# CubeShield.net
KiCad netlist of a schematic drawn in EAGLE
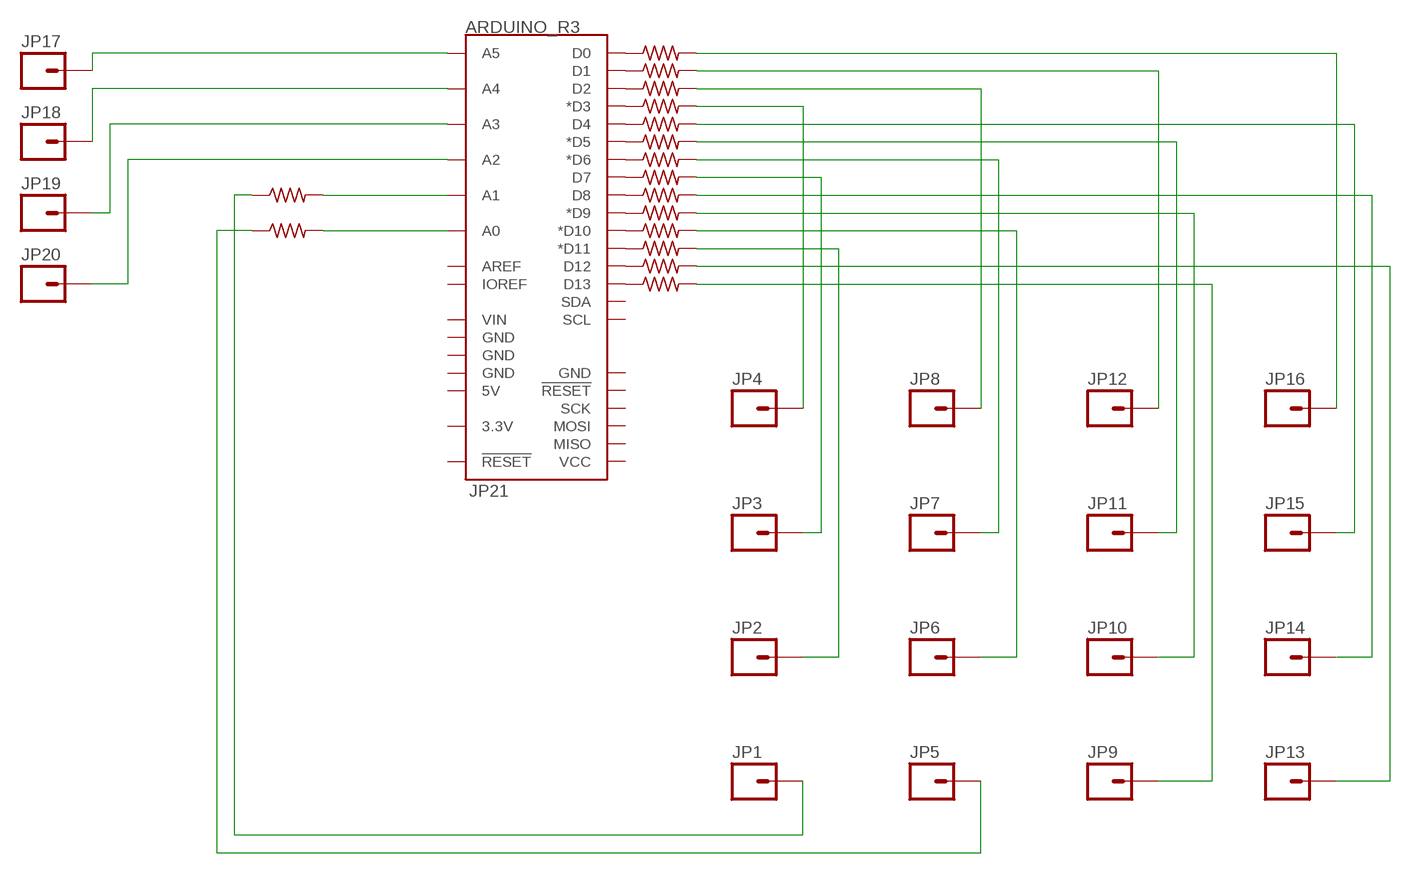
[diagram p0: schematic, sheet 1]

(export (version "E")
  (design (tool "Eeschema 10.0.6"))
  (components
    (comp (ref "JP1")
      (value "M01PTH_LONGPAD")
      (footprint "eagle-import:1X01_LONGPAD")
      (libsource (lib "eagle-import") (part "M01PTH_LONGPAD"))
    )
    (comp (ref "JP2")
      (value "M01PTH_LONGPAD")
      (footprint "eagle-import:1X01_LONGPAD")
      (libsource (lib "eagle-import") (part "M01PTH_LONGPAD"))
    )
    (comp (ref "JP3")
      (value "M01PTH_LONGPAD")
      (footprint "eagle-import:1X01_LONGPAD")
      (libsource (lib "eagle-import") (part "M01PTH_LONGPAD"))
    )
    (comp (ref "JP4")
      (value "M01PTH_LONGPAD")
      (footprint "eagle-import:1X01_LONGPAD")
      (libsource (lib "eagle-import") (part "M01PTH_LONGPAD"))
    )
    (comp (ref "JP5")
      (value "M01PTH_LONGPAD")
      (footprint "eagle-import:1X01_LONGPAD")
      (libsource (lib "eagle-import") (part "M01PTH_LONGPAD"))
    )
    (comp (ref "JP6")
      (value "M01PTH_LONGPAD")
      (footprint "eagle-import:1X01_LONGPAD")
      (libsource (lib "eagle-import") (part "M01PTH_LONGPAD"))
    )
    (comp (ref "JP7")
      (value "M01PTH_LONGPAD")
      (footprint "eagle-import:1X01_LONGPAD")
      (libsource (lib "eagle-import") (part "M01PTH_LONGPAD"))
    )
    (comp (ref "JP8")
      (value "M01PTH_LONGPAD")
      (footprint "eagle-import:1X01_LONGPAD")
      (libsource (lib "eagle-import") (part "M01PTH_LONGPAD"))
    )
    (comp (ref "JP9")
      (value "M01PTH_LONGPAD")
      (footprint "eagle-import:1X01_LONGPAD")
      (libsource (lib "eagle-import") (part "M01PTH_LONGPAD"))
    )
    (comp (ref "JP10")
      (value "M01PTH_LONGPAD")
      (footprint "eagle-import:1X01_LONGPAD")
      (libsource (lib "eagle-import") (part "M01PTH_LONGPAD"))
    )
    (comp (ref "JP11")
      (value "M01PTH_LONGPAD")
      (footprint "eagle-import:1X01_LONGPAD")
      (libsource (lib "eagle-import") (part "M01PTH_LONGPAD"))
    )
    (comp (ref "JP12")
      (value "M01PTH_LONGPAD")
      (footprint "eagle-import:1X01_LONGPAD")
      (libsource (lib "eagle-import") (part "M01PTH_LONGPAD"))
    )
    (comp (ref "JP13")
      (value "M01PTH_LONGPAD")
      (footprint "eagle-import:1X01_LONGPAD")
      (libsource (lib "eagle-import") (part "M01PTH_LONGPAD"))
    )
    (comp (ref "JP14")
      (value "M01PTH_LONGPAD")
      (footprint "eagle-import:1X01_LONGPAD")
      (libsource (lib "eagle-import") (part "M01PTH_LONGPAD"))
    )
    (comp (ref "JP15")
      (value "M01PTH_LONGPAD")
      (footprint "eagle-import:1X01_LONGPAD")
      (libsource (lib "eagle-import") (part "M01PTH_LONGPAD"))
    )
    (comp (ref "JP16")
      (value "M01PTH_LONGPAD")
      (footprint "eagle-import:1X01_LONGPAD")
      (libsource (lib "eagle-import") (part "M01PTH_LONGPAD"))
    )
    (comp (ref "JP17")
      (value "M01PTH_LONGPAD")
      (footprint "eagle-import:1X01_LONGPAD")
      (libsource (lib "eagle-import") (part "M01PTH_LONGPAD"))
    )
    (comp (ref "JP18")
      (value "M01PTH_LONGPAD")
      (footprint "eagle-import:1X01_LONGPAD")
      (libsource (lib "eagle-import") (part "M01PTH_LONGPAD"))
    )
    (comp (ref "JP19")
      (value "M01PTH_LONGPAD")
      (footprint "eagle-import:1X01_LONGPAD")
      (libsource (lib "eagle-import") (part "M01PTH_LONGPAD"))
    )
    (comp (ref "JP20")
      (value "M01PTH_LONGPAD")
      (footprint "eagle-import:1X01_LONGPAD")
      (libsource (lib "eagle-import") (part "M01PTH_LONGPAD"))
    )
    (comp (ref "JP21")
      (value "ARDUINO_R3")
      (footprint "eagle-import:ARDUINO_R3")
      (libsource (lib "eagle-import") (part "ARDUINO_R3"))
    )
    (comp (ref "R1")
      (value "R-US_0207/7")
      (footprint "eagle-import:0207_7")
      (libsource (lib "eagle-import") (part "R-US_0207/7"))
    )
    (comp (ref "R2")
      (value "R-US_0207/7")
      (footprint "eagle-import:0207_7")
      (libsource (lib "eagle-import") (part "R-US_0207/7"))
    )
    (comp (ref "R3")
      (value "R-US_0207/7")
      (footprint "eagle-import:0207_7")
      (libsource (lib "eagle-import") (part "R-US_0207/7"))
    )
    (comp (ref "R4")
      (value "R-US_0207/7")
      (footprint "eagle-import:0207_7")
      (libsource (lib "eagle-import") (part "R-US_0207/7"))
    )
    (comp (ref "R5")
      (value "R-US_0207/7")
      (footprint "eagle-import:0207_7")
      (libsource (lib "eagle-import") (part "R-US_0207/7"))
    )
    (comp (ref "R6")
      (value "R-US_0207/7")
      (footprint "eagle-import:0207_7")
      (libsource (lib "eagle-import") (part "R-US_0207/7"))
    )
    (comp (ref "R7")
      (value "R-US_0207/7")
      (footprint "eagle-import:0207_7")
      (libsource (lib "eagle-import") (part "R-US_0207/7"))
    )
    (comp (ref "R8")
      (value "R-US_0207/7")
      (footprint "eagle-import:0207_7")
      (libsource (lib "eagle-import") (part "R-US_0207/7"))
    )
    (comp (ref "R9")
      (value "R-US_0207/7")
      (footprint "eagle-import:0207_7")
      (libsource (lib "eagle-import") (part "R-US_0207/7"))
    )
    (comp (ref "R10")
      (value "R-US_0207/7")
      (footprint "eagle-import:0207_7")
      (libsource (lib "eagle-import") (part "R-US_0207/7"))
    )
    (comp (ref "R11")
      (value "R-US_0207/7")
      (footprint "eagle-import:0207_7")
      (libsource (lib "eagle-import") (part "R-US_0207/7"))
    )
    (comp (ref "R12")
      (value "R-US_0207/7")
      (footprint "eagle-import:0207_7")
      (libsource (lib "eagle-import") (part "R-US_0207/7"))
    )
    (comp (ref "R13")
      (value "R-US_0207/7")
      (footprint "eagle-import:0207_7")
      (libsource (lib "eagle-import") (part "R-US_0207/7"))
    )
    (comp (ref "R14")
      (value "R-US_0207/7")
      (footprint "eagle-import:0207_7")
      (libsource (lib "eagle-import") (part "R-US_0207/7"))
    )
    (comp (ref "R15")
      (value "R-US_0207/7")
      (footprint "eagle-import:0207_7")
      (libsource (lib "eagle-import") (part "R-US_0207/7"))
    )
    (comp (ref "R16")
      (value "R-US_0207/7")
      (footprint "eagle-import:0207_7")
      (libsource (lib "eagle-import") (part "R-US_0207/7"))
    )
  )
  (nets
    (net (code "1") (name "Net-(JP1-Pad1)") (class "Default")
      (node (ref "JP1") (pin "1") (pinfunction "1_1") (pintype "passive"))
      (node (ref "R16") (pin "1") (pinfunction "1_1") (pintype "passive"))
    )
    (net (code "2") (name "Net-(JP2-Pad1)") (class "Default")
      (node (ref "JP2") (pin "1") (pinfunction "1_1") (pintype "passive"))
      (node (ref "R12") (pin "2") (pinfunction "2_2") (pintype "passive"))
    )
    (net (code "3") (name "Net-(JP3-Pad1)") (class "Default")
      (node (ref "JP3") (pin "1") (pinfunction "1_1") (pintype "passive"))
      (node (ref "R8") (pin "2") (pinfunction "2_2") (pintype "passive"))
    )
    (net (code "4") (name "Net-(JP4-Pad1)") (class "Default")
      (node (ref "JP4") (pin "1") (pinfunction "1_1") (pintype "passive"))
      (node (ref "R4") (pin "2") (pinfunction "2_2") (pintype "passive"))
    )
    (net (code "5") (name "Net-(JP5-Pad1)") (class "Default")
      (node (ref "JP5") (pin "1") (pinfunction "1_1") (pintype "passive"))
      (node (ref "R15") (pin "1") (pinfunction "1_1") (pintype "passive"))
    )
    (net (code "6") (name "Net-(JP6-Pad1)") (class "Default")
      (node (ref "JP6") (pin "1") (pinfunction "1_1") (pintype "passive"))
      (node (ref "R11") (pin "2") (pinfunction "2_2") (pintype "passive"))
    )
    (net (code "7") (name "Net-(JP7-Pad1)") (class "Default")
      (node (ref "JP7") (pin "1") (pinfunction "1_1") (pintype "passive"))
      (node (ref "R7") (pin "2") (pinfunction "2_2") (pintype "passive"))
    )
    (net (code "8") (name "Net-(JP8-Pad1)") (class "Default")
      (node (ref "JP8") (pin "1") (pinfunction "1_1") (pintype "passive"))
      (node (ref "R3") (pin "2") (pinfunction "2_2") (pintype "passive"))
    )
    (net (code "9") (name "Net-(JP9-Pad1)") (class "Default")
      (node (ref "JP9") (pin "1") (pinfunction "1_1") (pintype "passive"))
      (node (ref "R14") (pin "2") (pinfunction "2_2") (pintype "passive"))
    )
    (net (code "10") (name "Net-(JP10-Pad1)") (class "Default")
      (node (ref "JP10") (pin "1") (pinfunction "1_1") (pintype "passive"))
      (node (ref "R10") (pin "2") (pinfunction "2_2") (pintype "passive"))
    )
    (net (code "11") (name "Net-(JP11-Pad1)") (class "Default")
      (node (ref "JP11") (pin "1") (pinfunction "1_1") (pintype "passive"))
      (node (ref "R6") (pin "2") (pinfunction "2_2") (pintype "passive"))
    )
    (net (code "12") (name "Net-(JP12-Pad1)") (class "Default")
      (node (ref "JP12") (pin "1") (pinfunction "1_1") (pintype "passive"))
      (node (ref "R2") (pin "2") (pinfunction "2_2") (pintype "passive"))
    )
    (net (code "13") (name "Net-(JP13-Pad1)") (class "Default")
      (node (ref "JP13") (pin "1") (pinfunction "1_1") (pintype "passive"))
      (node (ref "R13") (pin "2") (pinfunction "2_2") (pintype "passive"))
    )
    (net (code "14") (name "Net-(JP14-Pad1)") (class "Default")
      (node (ref "JP14") (pin "1") (pinfunction "1_1") (pintype "passive"))
      (node (ref "R9") (pin "2") (pinfunction "2_2") (pintype "passive"))
    )
    (net (code "15") (name "Net-(JP15-Pad1)") (class "Default")
      (node (ref "JP15") (pin "1") (pinfunction "1_1") (pintype "passive"))
      (node (ref "R5") (pin "2") (pinfunction "2_2") (pintype "passive"))
    )
    (net (code "16") (name "Net-(JP16-Pad1)") (class "Default")
      (node (ref "JP16") (pin "1") (pinfunction "1_1") (pintype "passive"))
      (node (ref "R1") (pin "2") (pinfunction "2_2") (pintype "passive"))
    )
    (net (code "17") (name "Net-(JP17-Pad1)") (class "Default")
      (node (ref "JP17") (pin "1") (pinfunction "1_1") (pintype "passive"))
      (node (ref "JP21") (pin "A5") (pinfunction "A5_A5") (pintype "bidirectional"))
    )
    (net (code "18") (name "Net-(JP18-Pad1)") (class "Default")
      (node (ref "JP18") (pin "1") (pinfunction "1_1") (pintype "passive"))
      (node (ref "JP21") (pin "A4") (pinfunction "A4_A4") (pintype "bidirectional"))
    )
    (net (code "19") (name "Net-(JP19-Pad1)") (class "Default")
      (node (ref "JP19") (pin "1") (pinfunction "1_1") (pintype "passive"))
      (node (ref "JP21") (pin "A3") (pinfunction "A3_A3") (pintype "bidirectional"))
    )
    (net (code "20") (name "Net-(JP20-Pad1)") (class "Default")
      (node (ref "JP20") (pin "1") (pinfunction "1_1") (pintype "passive"))
      (node (ref "JP21") (pin "A2") (pinfunction "A2_A2") (pintype "bidirectional"))
    )
    (net (code "21") (name "Net-(JP21-*D3)") (class "Default")
      (node (ref "JP21") (pin "D3") (pinfunction "*D3_D3") (pintype "bidirectional"))
      (node (ref "R4") (pin "1") (pinfunction "1_1") (pintype "passive"))
    )
    (net (code "22") (name "Net-(JP21-*D5)") (class "Default")
      (node (ref "JP21") (pin "D5") (pinfunction "*D5_D5") (pintype "bidirectional"))
      (node (ref "R6") (pin "1") (pinfunction "1_1") (pintype "passive"))
    )
    (net (code "23") (name "Net-(JP21-*D6)") (class "Default")
      (node (ref "JP21") (pin "D6") (pinfunction "*D6_D6") (pintype "bidirectional"))
      (node (ref "R7") (pin "1") (pinfunction "1_1") (pintype "passive"))
    )
    (net (code "24") (name "Net-(JP21-*D9)") (class "Default")
      (node (ref "JP21") (pin "D9") (pinfunction "*D9_D9") (pintype "bidirectional"))
      (node (ref "R10") (pin "1") (pinfunction "1_1") (pintype "passive"))
    )
    (net (code "25") (name "Net-(JP21-*D10)") (class "Default")
      (node (ref "JP21") (pin "D10") (pinfunction "*D10_D10") (pintype "bidirectional"))
      (node (ref "R11") (pin "1") (pinfunction "1_1") (pintype "passive"))
    )
    (net (code "26") (name "Net-(JP21-*D11)") (class "Default")
      (node (ref "JP21") (pin "D11") (pinfunction "*D11_D11") (pintype "bidirectional"))
      (node (ref "R12") (pin "1") (pinfunction "1_1") (pintype "passive"))
    )
    (net (code "27") (name "Net-(JP21-PadA0)") (class "Default")
      (node (ref "JP21") (pin "A0") (pinfunction "A0_A0") (pintype "bidirectional"))
      (node (ref "R15") (pin "2") (pinfunction "2_2") (pintype "passive"))
    )
    (net (code "28") (name "Net-(JP21-PadA1)") (class "Default")
      (node (ref "JP21") (pin "A1") (pinfunction "A1_A1") (pintype "bidirectional"))
      (node (ref "R16") (pin "2") (pinfunction "2_2") (pintype "passive"))
    )
    (net (code "29") (name "Net-(JP21-PadD0)") (class "Default")
      (node (ref "JP21") (pin "D0") (pinfunction "D0_D0") (pintype "bidirectional"))
      (node (ref "R1") (pin "1") (pinfunction "1_1") (pintype "passive"))
    )
    (net (code "30") (name "Net-(JP21-PadD1)") (class "Default")
      (node (ref "JP21") (pin "D1") (pinfunction "D1_D1") (pintype "bidirectional"))
      (node (ref "R2") (pin "1") (pinfunction "1_1") (pintype "passive"))
    )
    (net (code "31") (name "Net-(JP21-PadD2)") (class "Default")
      (node (ref "JP21") (pin "D2") (pinfunction "D2_D2") (pintype "bidirectional"))
      (node (ref "R3") (pin "1") (pinfunction "1_1") (pintype "passive"))
    )
    (net (code "32") (name "Net-(JP21-PadD4)") (class "Default")
      (node (ref "JP21") (pin "D4") (pinfunction "D4_D4") (pintype "bidirectional"))
      (node (ref "R5") (pin "1") (pinfunction "1_1") (pintype "passive"))
    )
    (net (code "33") (name "Net-(JP21-PadD7)") (class "Default")
      (node (ref "JP21") (pin "D7") (pinfunction "D7_D7") (pintype "bidirectional"))
      (node (ref "R8") (pin "1") (pinfunction "1_1") (pintype "passive"))
    )
    (net (code "34") (name "Net-(JP21-PadD8)") (class "Default")
      (node (ref "JP21") (pin "D8") (pinfunction "D8_D8") (pintype "bidirectional"))
      (node (ref "R9") (pin "1") (pinfunction "1_1") (pintype "passive"))
    )
    (net (code "35") (name "Net-(JP21-PadD12)") (class "Default")
      (node (ref "JP21") (pin "D12") (pinfunction "D12_D12") (pintype "bidirectional"))
      (node (ref "R13") (pin "1") (pinfunction "1_1") (pintype "passive"))
    )
    (net (code "36") (name "Net-(JP21-PadD13)") (class "Default")
      (node (ref "JP21") (pin "D13") (pinfunction "D13_D13") (pintype "bidirectional"))
      (node (ref "R14") (pin "1") (pinfunction "1_1") (pintype "passive"))
    )
    (net (code "37") (name "unconnected-(JP21-GND-PadGND@1)") (class "Default")
      (node (ref "JP21") (pin "GND@1") (pinfunction "GND_GND@1") (pintype "bidirectional"))
    )
    (net (code "38") (name "unconnected-(JP21-GND-PadGND@2)") (class "Default")
      (node (ref "JP21") (pin "GND@2") (pinfunction "GND_GND@2") (pintype "bidirectional"))
    )
    (net (code "39") (name "unconnected-(JP21-GND-PadGND@3)") (class "Default")
      (node (ref "JP21") (pin "GND@3") (pinfunction "GND_GND@3") (pintype "bidirectional"))
    )
    (net (code "40") (name "unconnected-(JP21-GND-PadGND@4)") (class "Default")
      (node (ref "JP21") (pin "GND@4") (pinfunction "GND_GND@4") (pintype "bidirectional"))
    )
    (net (code "41") (name "unconnected-(JP21-Pad3.3V)") (class "Default")
      (node (ref "JP21") (pin "3.3V") (pinfunction "3.3V_3.3V") (pintype "bidirectional"))
    )
    (net (code "42") (name "unconnected-(JP21-Pad5V)") (class "Default")
      (node (ref "JP21") (pin "5V") (pinfunction "5V_5V") (pintype "bidirectional"))
    )
    (net (code "43") (name "unconnected-(JP21-PadAREF)") (class "Default")
      (node (ref "JP21") (pin "AREF") (pinfunction "AREF_AREF") (pintype "bidirectional"))
    )
    (net (code "44") (name "unconnected-(JP21-PadIOREF)") (class "Default")
      (node (ref "JP21") (pin "IOREF") (pinfunction "IOREF_IOREF") (pintype "bidirectional"))
    )
    (net (code "45") (name "unconnected-(JP21-PadMISO)") (class "Default")
      (node (ref "JP21") (pin "MISO") (pinfunction "MISO_MISO") (pintype "bidirectional"))
    )
    (net (code "46") (name "unconnected-(JP21-PadMOSI)") (class "Default")
      (node (ref "JP21") (pin "MOSI") (pinfunction "MOSI_MOSI") (pintype "bidirectional"))
    )
    (net (code "47") (name "unconnected-(JP21-PadSCK)") (class "Default")
      (node (ref "JP21") (pin "SCK") (pinfunction "SCK_SCK") (pintype "bidirectional"))
    )
    (net (code "48") (name "unconnected-(JP21-PadSCL)") (class "Default")
      (node (ref "JP21") (pin "SCL") (pinfunction "SCL_SCL") (pintype "bidirectional"))
    )
    (net (code "49") (name "unconnected-(JP21-PadSDA)") (class "Default")
      (node (ref "JP21") (pin "SDA") (pinfunction "SDA_SDA") (pintype "bidirectional"))
    )
    (net (code "50") (name "unconnected-(JP21-PadVCC)") (class "Default")
      (node (ref "JP21") (pin "VCC") (pinfunction "VCC_VCC") (pintype "bidirectional"))
    )
    (net (code "51") (name "unconnected-(JP21-PadVIN)") (class "Default")
      (node (ref "JP21") (pin "VIN") (pinfunction "VIN_VIN") (pintype "bidirectional"))
    )
    (net (code "52") (name "unconnected-(JP21-~{RESET}-PadRESET@1)") (class "Default")
      (node (ref "JP21") (pin "RESET@1") (pinfunction "~{RESET}_RESET@1") (pintype "bidirectional"))
    )
    (net (code "53") (name "unconnected-(JP21-~{RESET}-PadRESET@2)") (class "Default")
      (node (ref "JP21") (pin "RESET@2") (pinfunction "~{RESET}_RESET@2") (pintype "bidirectional"))
    )
  )
)
